# RP2040_Conn.net
KiCad netlist of a schematic drawn in Altium Designer
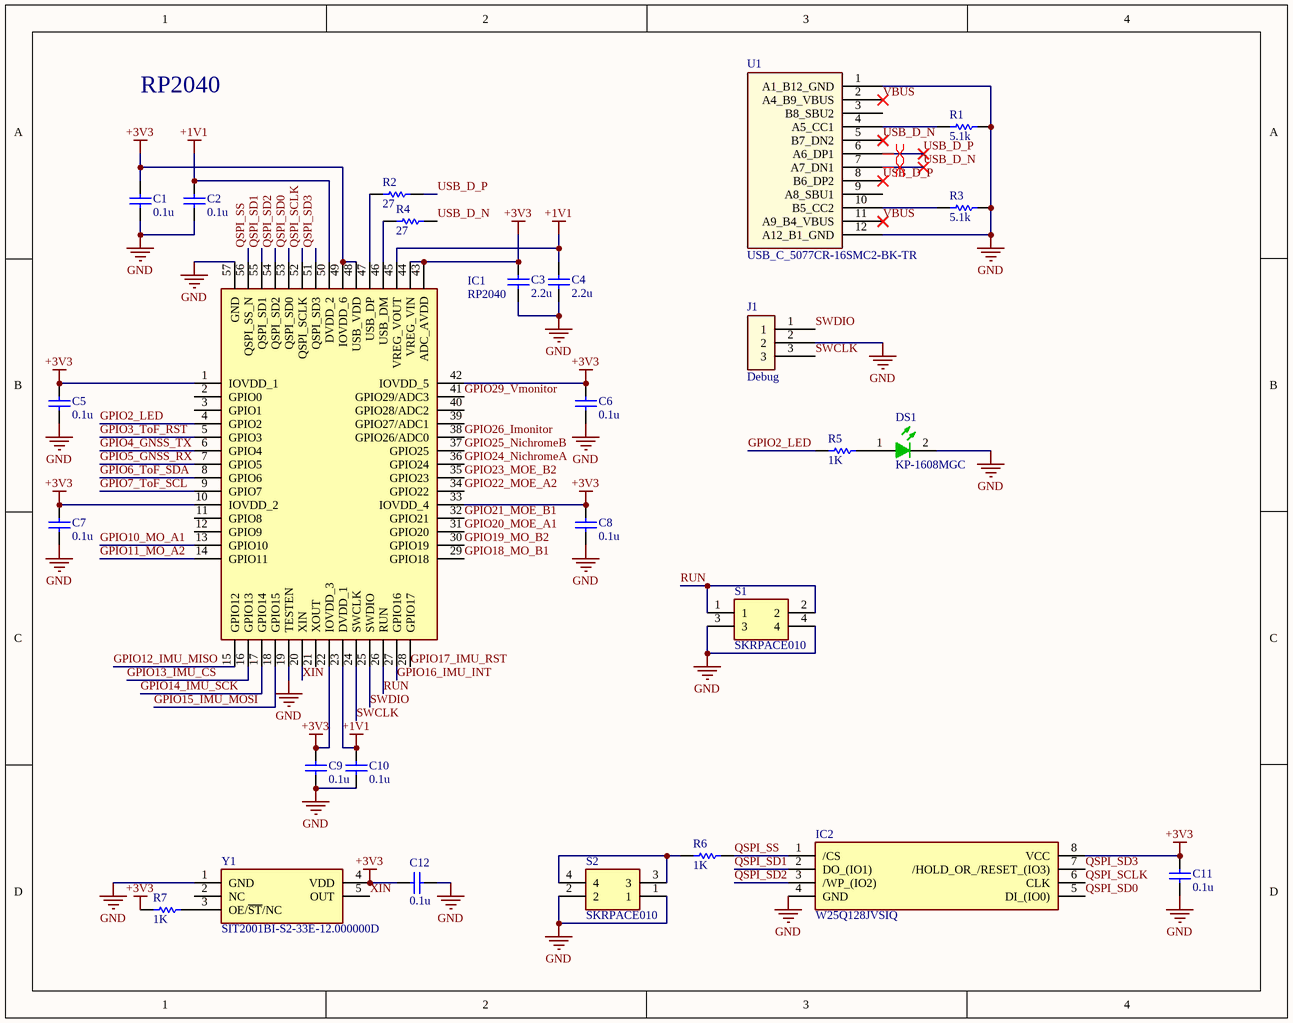
[diagram p0: RP2040_Conn.SchDoc]

(export (version "E")
  (design (tool "Eeschema 10.0.6"))
  (components
    (comp (ref "C1")
      (value "0.1u")
      (footprint "1608[0603]")
      (description "Capacitor")
      (libsource (lib "Simulation Generic Components") (part "Capacitor"))
    )
    (comp (ref "C2")
      (value "0.1u")
      (footprint "1608[0603]")
      (description "Capacitor")
      (libsource (lib "Simulation Generic Components") (part "Capacitor"))
    )
    (comp (ref "C3")
      (value "2.2u")
      (footprint "1608[0603]")
      (description "Capacitor")
      (libsource (lib "Simulation Generic Components") (part "Capacitor"))
    )
    (comp (ref "C4")
      (value "2.2u")
      (footprint "1608[0603]")
      (description "Capacitor")
      (libsource (lib "Simulation Generic Components") (part "Capacitor"))
    )
    (comp (ref "C5")
      (value "0.1u")
      (footprint "1608[0603]")
      (description "Capacitor")
      (libsource (lib "Simulation Generic Components") (part "Capacitor"))
    )
    (comp (ref "C6")
      (value "0.1u")
      (footprint "1608[0603]")
      (description "Capacitor")
      (libsource (lib "Simulation Generic Components") (part "Capacitor"))
    )
    (comp (ref "C7")
      (value "0.1u")
      (footprint "1608[0603]")
      (description "Capacitor")
      (libsource (lib "Simulation Generic Components") (part "Capacitor"))
    )
    (comp (ref "C8")
      (value "0.1u")
      (footprint "1608[0603]")
      (description "Capacitor")
      (libsource (lib "Simulation Generic Components") (part "Capacitor"))
    )
    (comp (ref "C9")
      (value "0.1u")
      (footprint "1608[0603]")
      (description "Capacitor")
      (libsource (lib "Simulation Generic Components") (part "Capacitor"))
    )
    (comp (ref "C10")
      (value "0.1u")
      (footprint "1608[0603]")
      (description "Capacitor")
      (libsource (lib "Simulation Generic Components") (part "Capacitor"))
    )
    (comp (ref "C11")
      (value "0.1u")
      (footprint "1608[0603]")
      (description "Capacitor")
      (libsource (lib "Simulation Generic Components") (part "Capacitor"))
    )
    (comp (ref "C12")
      (value "0.1u")
      (footprint "1608[0603]")
      (description "Capacitor")
      (libsource (lib "Simulation Generic Components") (part "Capacitor"))
    )
    (comp (ref "DS1")
      (value "KP-1608MGC")
      (footprint "KING-0603LED_GREEN_V")
      (description "LED, SMT, 0603(1608), 1.1mm thickness, Green")
      (fields (field (name "MANUFACTURER") "Kingbright"))
      (libsource (lib "Altium Content Vault") (part "KING-LED-GREEN-A1K2-2"))
    )
    (comp (ref "IC1")
      (value "RP2040")
      (footprint "SamacSys:QFN40P700X700X90-57N-D")
      (description "Integrated Circuit")
      (libsource (lib "*") (part "RP2040"))
    )
    (comp (ref "IC2")
      (value "W25Q128JVSIQ")
      (footprint "SamacSys:SOIC127P790X216-8N")
      (description "Integrated Circuit")
      (fields (field (name "MOUSER PART NUMBER") "454-W25Q128JVSIQ"))
      (libsource (lib "*") (part "W25Q128JVSIQ"))
    )
    (comp (ref "J1")
      (value "Debug")
      (footprint "PinHeader_0.65_3_Half")
      (libsource (lib "tanekonsat_lib") (part "PinHeader_0.65_3_Half"))
    )
    (comp (ref "R1")
      (value "5.1k")
      (footprint "1608[0603]")
      (description "Resistor")
      (libsource (lib "Simulation Generic Components") (part "Resistor"))
    )
    (comp (ref "R2")
      (value "27")
      (footprint "1608[0603]")
      (description "Resistor")
      (libsource (lib "Simulation Generic Components") (part "Resistor"))
    )
    (comp (ref "R3")
      (value "5.1k")
      (footprint "1608[0603]")
      (description "Resistor")
      (libsource (lib "Simulation Generic Components") (part "Resistor"))
    )
    (comp (ref "R4")
      (value "27")
      (footprint "1608[0603]")
      (description "Resistor")
      (libsource (lib "Simulation Generic Components") (part "Resistor"))
    )
    (comp (ref "R5")
      (value "1K")
      (footprint "1608[0603]")
      (description "Resistor")
      (libsource (lib "Simulation Generic Components") (part "Resistor"))
    )
    (comp (ref "R6")
      (value "1K")
      (footprint "1608[0603]")
      (description "Resistor")
      (libsource (lib "Simulation Generic Components") (part "Resistor"))
    )
    (comp (ref "R7")
      (value "1K")
      (footprint "1608[0603]")
      (description "Resistor")
      (libsource (lib "Simulation Generic Components") (part "Resistor"))
    )
    (comp (ref "S1")
      (value "SKRPACE010")
      (footprint "SamacSys:SMT(4.2X3.2)")
      (description "Switch")
      (fields (field (name "MOUSER PART NUMBER") "688-SKRPACE010"))
      (libsource (lib "*") (part "SKRPACE010"))
    )
    (comp (ref "S2")
      (value "SKRPACE010")
      (footprint "SamacSys:SMT(4.2X3.2)")
      (description "Switch")
      (fields (field (name "MOUSER PART NUMBER") "688-SKRPACE010"))
      (libsource (lib "") (part "SKRPACE010_1"))
    )
    (comp (ref "U1")
      (value "USB_C_5077CR-16SMC2-BK-TR")
      (footprint "USB_C_5077CR-16SMC2-BK-TR")
      (libsource (lib "tanekonsat_lib") (part "USB_C_5077CR-16SMC2-BK-TR"))
    )
    (comp (ref "Y1")
      (value "SIT2001BI-S2-33E-12.000000D")
      (footprint "SamacSys:SOT95P280X145-5N")
      (description "Crystal or Oscillator")
      (libsource (lib "*") (part "SIT2001BI-S2-33E-12.000000D"))
    )
  )
  (nets
    (net (code "1") (name "+1V1") (class "Default")
      (node (ref "C10") (pin "1") (pinfunction "1_1") (pintype "passive"))
      (node (ref "C2") (pin "2") (pinfunction "2_2") (pintype "passive"))
      (node (ref "C4") (pin "2") (pinfunction "2_2") (pintype "passive"))
      (node (ref "IC1") (pin "23") (pinfunction "DVDD_1_23") (pintype "passive"))
      (node (ref "IC1") (pin "45") (pinfunction "VREG_VOUT_45") (pintype "passive"))
      (node (ref "IC1") (pin "50") (pinfunction "DVDD_2_50") (pintype "passive"))
    )
    (net (code "2") (name "+3V3") (class "Default")
      (node (ref "C1") (pin "2") (pinfunction "2_2") (pintype "passive"))
      (node (ref "C11") (pin "2") (pinfunction "2_2") (pintype "passive"))
      (node (ref "C12") (pin "1") (pinfunction "1_1") (pintype "passive"))
      (node (ref "C3") (pin "2") (pinfunction "2_2") (pintype "passive"))
      (node (ref "C5") (pin "2") (pinfunction "2_2") (pintype "passive"))
      (node (ref "C6") (pin "1") (pinfunction "1_1") (pintype "passive"))
      (node (ref "C7") (pin "1") (pinfunction "1_1") (pintype "passive"))
      (node (ref "C8") (pin "1") (pinfunction "1_1") (pintype "passive"))
      (node (ref "C9") (pin "1") (pinfunction "1_1") (pintype "passive"))
      (node (ref "IC1") (pin "1") (pinfunction "IOVDD_1_1") (pintype "passive"))
      (node (ref "IC1") (pin "10") (pinfunction "IOVDD_2_10") (pintype "passive"))
      (node (ref "IC1") (pin "22") (pinfunction "IOVDD_3_22") (pintype "passive"))
      (node (ref "IC1") (pin "33") (pinfunction "IOVDD_4_33") (pintype "passive"))
      (node (ref "IC1") (pin "42") (pinfunction "IOVDD_5_42") (pintype "passive"))
      (node (ref "IC1") (pin "43") (pinfunction "ADC_AVDD_43") (pintype "passive"))
      (node (ref "IC1") (pin "44") (pinfunction "VREG_VIN_44") (pintype "passive"))
      (node (ref "IC1") (pin "48") (pinfunction "USB_VDD_48") (pintype "passive"))
      (node (ref "IC1") (pin "49") (pinfunction "IOVDD_6_49") (pintype "passive"))
      (node (ref "IC2") (pin "8") (pinfunction "VCC_8") (pintype "passive"))
      (node (ref "R7") (pin "1") (pinfunction "1_1") (pintype "passive"))
      (node (ref "Y1") (pin "4") (pinfunction "VDD_4") (pintype "passive"))
    )
    (net (code "3") (name "/GPIO2_LED") (class "Default")
      (node (ref "IC1") (pin "4") (pinfunction "GPIO2_4") (pintype "passive"))
      (node (ref "R5") (pin "1") (pinfunction "1_1") (pintype "passive"))
    )
    (net (code "4") (name "/GPIO3_ToF_RST") (class "Default")
      (node (ref "IC1") (pin "5") (pinfunction "GPIO3_5") (pintype "passive"))
    )
    (net (code "5") (name "/GPIO4_GNSS_TX") (class "Default")
      (node (ref "IC1") (pin "6") (pinfunction "GPIO4_6") (pintype "passive"))
    )
    (net (code "6") (name "/GPIO5_GNSS_RX") (class "Default")
      (node (ref "IC1") (pin "7") (pinfunction "GPIO5_7") (pintype "passive"))
    )
    (net (code "7") (name "/GPIO6_ToF_SDA") (class "Default")
      (node (ref "IC1") (pin "8") (pinfunction "GPIO6_8") (pintype "passive"))
    )
    (net (code "8") (name "/GPIO7_ToF_SCL") (class "Default")
      (node (ref "IC1") (pin "9") (pinfunction "GPIO7_9") (pintype "passive"))
    )
    (net (code "9") (name "/GPIO10_MO_A1") (class "Default")
      (node (ref "IC1") (pin "13") (pinfunction "GPIO10_13") (pintype "passive"))
    )
    (net (code "10") (name "/GPIO11_MO_A2") (class "Default")
      (node (ref "IC1") (pin "14") (pinfunction "GPIO11_14") (pintype "passive"))
    )
    (net (code "11") (name "/GPIO12_IMU_MISO") (class "Default")
      (node (ref "IC1") (pin "15") (pinfunction "GPIO12_15") (pintype "passive"))
    )
    (net (code "12") (name "/GPIO13_IMU_CS") (class "Default")
      (node (ref "IC1") (pin "16") (pinfunction "GPIO13_16") (pintype "passive"))
    )
    (net (code "13") (name "/GPIO14_IMU_SCK") (class "Default")
      (node (ref "IC1") (pin "17") (pinfunction "GPIO14_17") (pintype "passive"))
    )
    (net (code "14") (name "/GPIO15_IMU_MOSI") (class "Default")
      (node (ref "IC1") (pin "18") (pinfunction "GPIO15_18") (pintype "passive"))
    )
    (net (code "15") (name "/GPIO16_IMU_INT") (class "Default")
      (node (ref "IC1") (pin "27") (pinfunction "GPIO16_27") (pintype "passive"))
    )
    (net (code "16") (name "/GPIO17_IMU_RST") (class "Default")
      (node (ref "IC1") (pin "28") (pinfunction "GPIO17_28") (pintype "passive"))
    )
    (net (code "17") (name "/GPIO18_MO_B1") (class "Default")
      (node (ref "IC1") (pin "29") (pinfunction "GPIO18_29") (pintype "passive"))
    )
    (net (code "18") (name "/GPIO19_MO_B2") (class "Default")
      (node (ref "IC1") (pin "30") (pinfunction "GPIO19_30") (pintype "passive"))
    )
    (net (code "19") (name "/GPIO20_MOE_A1") (class "Default")
      (node (ref "IC1") (pin "31") (pinfunction "GPIO20_31") (pintype "passive"))
    )
    (net (code "20") (name "/GPIO21_MOE_B1") (class "Default")
      (node (ref "IC1") (pin "32") (pinfunction "GPIO21_32") (pintype "passive"))
    )
    (net (code "21") (name "/GPIO22_MOE_A2") (class "Default")
      (node (ref "IC1") (pin "34") (pinfunction "GPIO22_34") (pintype "passive"))
    )
    (net (code "22") (name "/GPIO23_MOE_B2") (class "Default")
      (node (ref "IC1") (pin "35") (pinfunction "GPIO23_35") (pintype "passive"))
    )
    (net (code "23") (name "/GPIO24_NichromeA") (class "Default")
      (node (ref "IC1") (pin "36") (pinfunction "GPIO24_36") (pintype "passive"))
    )
    (net (code "24") (name "/GPIO25_NichromeB") (class "Default")
      (node (ref "IC1") (pin "37") (pinfunction "GPIO25_37") (pintype "passive"))
    )
    (net (code "25") (name "/GPIO26_Imonitor") (class "Default")
      (node (ref "IC1") (pin "38") (pinfunction "GPIO26/ADC0_38") (pintype "passive"))
    )
    (net (code "26") (name "/GPIO29_Vmonitor") (class "Default")
      (node (ref "IC1") (pin "41") (pinfunction "GPIO29/ADC3_41") (pintype "passive"))
    )
    (net (code "27") (name "/QSPI_SCLK") (class "Default")
      (node (ref "IC1") (pin "52") (pinfunction "QSPI_SCLK_52") (pintype "passive"))
      (node (ref "IC2") (pin "6") (pinfunction "CLK_6") (pintype "passive"))
    )
    (net (code "28") (name "/QSPI_SD0") (class "Default")
      (node (ref "IC1") (pin "53") (pinfunction "QSPI_SD0_53") (pintype "passive"))
      (node (ref "IC2") (pin "5") (pinfunction "DI_(IO0)_5") (pintype "passive"))
    )
    (net (code "29") (name "/QSPI_SD1") (class "Default")
      (node (ref "IC1") (pin "55") (pinfunction "QSPI_SD1_55") (pintype "passive"))
      (node (ref "IC2") (pin "2") (pinfunction "DO_(IO1)_2") (pintype "passive"))
    )
    (net (code "30") (name "/QSPI_SD2") (class "Default")
      (node (ref "IC1") (pin "54") (pinfunction "QSPI_SD2_54") (pintype "passive"))
      (node (ref "IC2") (pin "3") (pinfunction "/WP_(IO2)_3") (pintype "passive"))
    )
    (net (code "31") (name "/QSPI_SD3") (class "Default")
      (node (ref "IC1") (pin "51") (pinfunction "QSPI_SD3_51") (pintype "passive"))
      (node (ref "IC2") (pin "7") (pinfunction "/HOLD_OR_/RESET_(IO3)_7") (pintype "passive"))
    )
    (net (code "32") (name "/QSPI_SS") (class "Default")
      (node (ref "IC1") (pin "56") (pinfunction "QSPI_SS_N_56") (pintype "passive"))
      (node (ref "IC2") (pin "1") (pinfunction "/CS_1") (pintype "passive"))
      (node (ref "R6") (pin "2") (pinfunction "2_2") (pintype "passive"))
    )
    (net (code "33") (name "/RUN") (class "Default")
      (node (ref "IC1") (pin "26") (pinfunction "RUN_26") (pintype "passive"))
      (node (ref "S1") (pin "1") (pinfunction "1_1") (pintype "passive"))
      (node (ref "S1") (pin "2") (pinfunction "2_2") (pintype "passive"))
    )
    (net (code "34") (name "/SWCLK") (class "Default")
      (node (ref "IC1") (pin "24") (pinfunction "SWCLK_24") (pintype "passive"))
      (node (ref "J1") (pin "3") (pinfunction "3_3") (pintype "passive"))
    )
    (net (code "35") (name "/SWDIO") (class "Default")
      (node (ref "IC1") (pin "25") (pinfunction "SWDIO_25") (pintype "passive"))
      (node (ref "J1") (pin "1") (pinfunction "1_1") (pintype "passive"))
    )
    (net (code "36") (name "/USB_D_N") (class "Default")
      (node (ref "R4") (pin "2") (pinfunction "2_2") (pintype "passive"))
      (node (ref "U1") (pin "5") (pinfunction "B7_DN2_5") (pintype "passive"))
      (node (ref "U1") (pin "7") (pinfunction "A7_DN1_7") (pintype "passive"))
    )
    (net (code "37") (name "/USB_D_P") (class "Default")
      (node (ref "R2") (pin "2") (pinfunction "2_2") (pintype "passive"))
      (node (ref "U1") (pin "6") (pinfunction "A6_DP1_6") (pintype "passive"))
      (node (ref "U1") (pin "8") (pinfunction "B6_DP2_8") (pintype "passive"))
    )
    (net (code "38") (name "/VBUS") (class "Default")
      (node (ref "U1") (pin "11") (pinfunction "A9_B4_VBUS_11") (pintype "passive"))
      (node (ref "U1") (pin "2") (pinfunction "A4_B9_VBUS_2") (pintype "passive"))
    )
    (net (code "39") (name "/XIN") (class "Default")
      (node (ref "IC1") (pin "20") (pinfunction "XIN_20") (pintype "passive"))
      (node (ref "Y1") (pin "5") (pinfunction "OUT_5") (pintype "passive"))
    )
    (net (code "40") (name "GND") (class "Default")
      (node (ref "C1") (pin "1") (pinfunction "1_1") (pintype "passive"))
      (node (ref "C10") (pin "2") (pinfunction "2_2") (pintype "passive"))
      (node (ref "C11") (pin "1") (pinfunction "1_1") (pintype "passive"))
      (node (ref "C12") (pin "2") (pinfunction "2_2") (pintype "passive"))
      (node (ref "C2") (pin "1") (pinfunction "1_1") (pintype "passive"))
      (node (ref "C3") (pin "1") (pinfunction "1_1") (pintype "passive"))
      (node (ref "C4") (pin "1") (pinfunction "1_1") (pintype "passive"))
      (node (ref "C5") (pin "1") (pinfunction "1_1") (pintype "passive"))
      (node (ref "C6") (pin "2") (pinfunction "2_2") (pintype "passive"))
      (node (ref "C7") (pin "2") (pinfunction "2_2") (pintype "passive"))
      (node (ref "C8") (pin "2") (pinfunction "2_2") (pintype "passive"))
      (node (ref "C9") (pin "2") (pinfunction "2_2") (pintype "passive"))
      (node (ref "DS1") (pin "2") (pinfunction "K_2") (pintype "passive"))
      (node (ref "IC1") (pin "19") (pinfunction "TESTEN_19") (pintype "passive"))
      (node (ref "IC1") (pin "57") (pinfunction "GND_57") (pintype "passive"))
      (node (ref "IC2") (pin "4") (pinfunction "GND_4") (pintype "passive"))
      (node (ref "J1") (pin "2") (pinfunction "2_2") (pintype "passive"))
      (node (ref "R1") (pin "2") (pinfunction "2_2") (pintype "passive"))
      (node (ref "R3") (pin "2") (pinfunction "2_2") (pintype "passive"))
      (node (ref "S1") (pin "3") (pinfunction "3_3") (pintype "passive"))
      (node (ref "S1") (pin "4") (pinfunction "4_4") (pintype "passive"))
      (node (ref "S2") (pin "1") (pinfunction "1_1") (pintype "passive"))
      (node (ref "S2") (pin "2") (pinfunction "2_2") (pintype "passive"))
      (node (ref "U1") (pin "1") (pinfunction "A1_B12_GND_1") (pintype "passive"))
      (node (ref "U1") (pin "12") (pinfunction "A12_B1_GND_12") (pintype "passive"))
      (node (ref "Y1") (pin "1") (pinfunction "GND_1") (pintype "passive"))
    )
    (net (code "41") (name "Net-(DS1-A)") (class "Default")
      (node (ref "DS1") (pin "1") (pinfunction "A_1") (pintype "passive"))
      (node (ref "R5") (pin "2") (pinfunction "2_2") (pintype "passive"))
    )
    (net (code "42") (name "Net-(IC1-USB_DM)") (class "Default")
      (node (ref "IC1") (pin "46") (pinfunction "USB_DM_46") (pintype "passive"))
      (node (ref "R4") (pin "1") (pinfunction "1_1") (pintype "passive"))
    )
    (net (code "43") (name "Net-(IC1-USB_DP)") (class "Default")
      (node (ref "IC1") (pin "47") (pinfunction "USB_DP_47") (pintype "passive"))
      (node (ref "R2") (pin "1") (pinfunction "1_1") (pintype "passive"))
    )
    (net (code "44") (name "Net-(R6-Pad1)") (class "Default")
      (node (ref "R6") (pin "1") (pinfunction "1_1") (pintype "passive"))
      (node (ref "S2") (pin "3") (pinfunction "3_3") (pintype "passive"))
      (node (ref "S2") (pin "4") (pinfunction "4_4") (pintype "passive"))
    )
    (net (code "45") (name "Net-(U1-A5_CC1)") (class "Default")
      (node (ref "R1") (pin "1") (pinfunction "1_1") (pintype "passive"))
      (node (ref "U1") (pin "4") (pinfunction "A5_CC1_4") (pintype "passive"))
    )
    (net (code "46") (name "Net-(U1-B5_CC2)") (class "Default")
      (node (ref "R3") (pin "1") (pinfunction "1_1") (pintype "passive"))
      (node (ref "U1") (pin "10") (pinfunction "B5_CC2_10") (pintype "passive"))
    )
    (net (code "47") (name "Net-(Y1-OE{slash}~{ST}{slash}NC)") (class "Default")
      (node (ref "R7") (pin "2") (pinfunction "2_2") (pintype "passive"))
      (node (ref "Y1") (pin "3") (pinfunction "OE/~{ST}/NC_3") (pintype "passive"))
    )
    (net (code "48") (name "unconnected-(IC1-GPIO0-Pad2)") (class "Default")
      (node (ref "IC1") (pin "2") (pinfunction "GPIO0_2") (pintype "passive"))
    )
    (net (code "49") (name "unconnected-(IC1-GPIO1-Pad3)") (class "Default")
      (node (ref "IC1") (pin "3") (pinfunction "GPIO1_3") (pintype "passive"))
    )
    (net (code "50") (name "unconnected-(IC1-GPIO8-Pad11)") (class "Default")
      (node (ref "IC1") (pin "11") (pinfunction "GPIO8_11") (pintype "passive"))
    )
    (net (code "51") (name "unconnected-(IC1-GPIO9-Pad12)") (class "Default")
      (node (ref "IC1") (pin "12") (pinfunction "GPIO9_12") (pintype "passive"))
    )
    (net (code "52") (name "unconnected-(IC1-GPIO27{slash}ADC1-Pad39)") (class "Default")
      (node (ref "IC1") (pin "39") (pinfunction "GPIO27/ADC1_39") (pintype "passive"))
    )
    (net (code "53") (name "unconnected-(IC1-GPIO28{slash}ADC2-Pad40)") (class "Default")
      (node (ref "IC1") (pin "40") (pinfunction "GPIO28/ADC2_40") (pintype "passive"))
    )
    (net (code "54") (name "unconnected-(IC1-XOUT-Pad21)") (class "Default")
      (node (ref "IC1") (pin "21") (pinfunction "XOUT_21") (pintype "passive"))
    )
    (net (code "55") (name "unconnected-(U1-A8_SBU1-Pad9)") (class "Default")
      (node (ref "U1") (pin "9") (pinfunction "A8_SBU1_9") (pintype "passive"))
    )
    (net (code "56") (name "unconnected-(U1-B8_SBU2-Pad3)") (class "Default")
      (node (ref "U1") (pin "3") (pinfunction "B8_SBU2_3") (pintype "passive"))
    )
    (net (code "57") (name "unconnected-(Y1-NC-Pad2)") (class "Default")
      (node (ref "Y1") (pin "2") (pinfunction "NC_2") (pintype "passive"))
    )
  )
)
